# sensor_16_analog.net
KiCad netlist of a schematic drawn in EasyEDA Pro
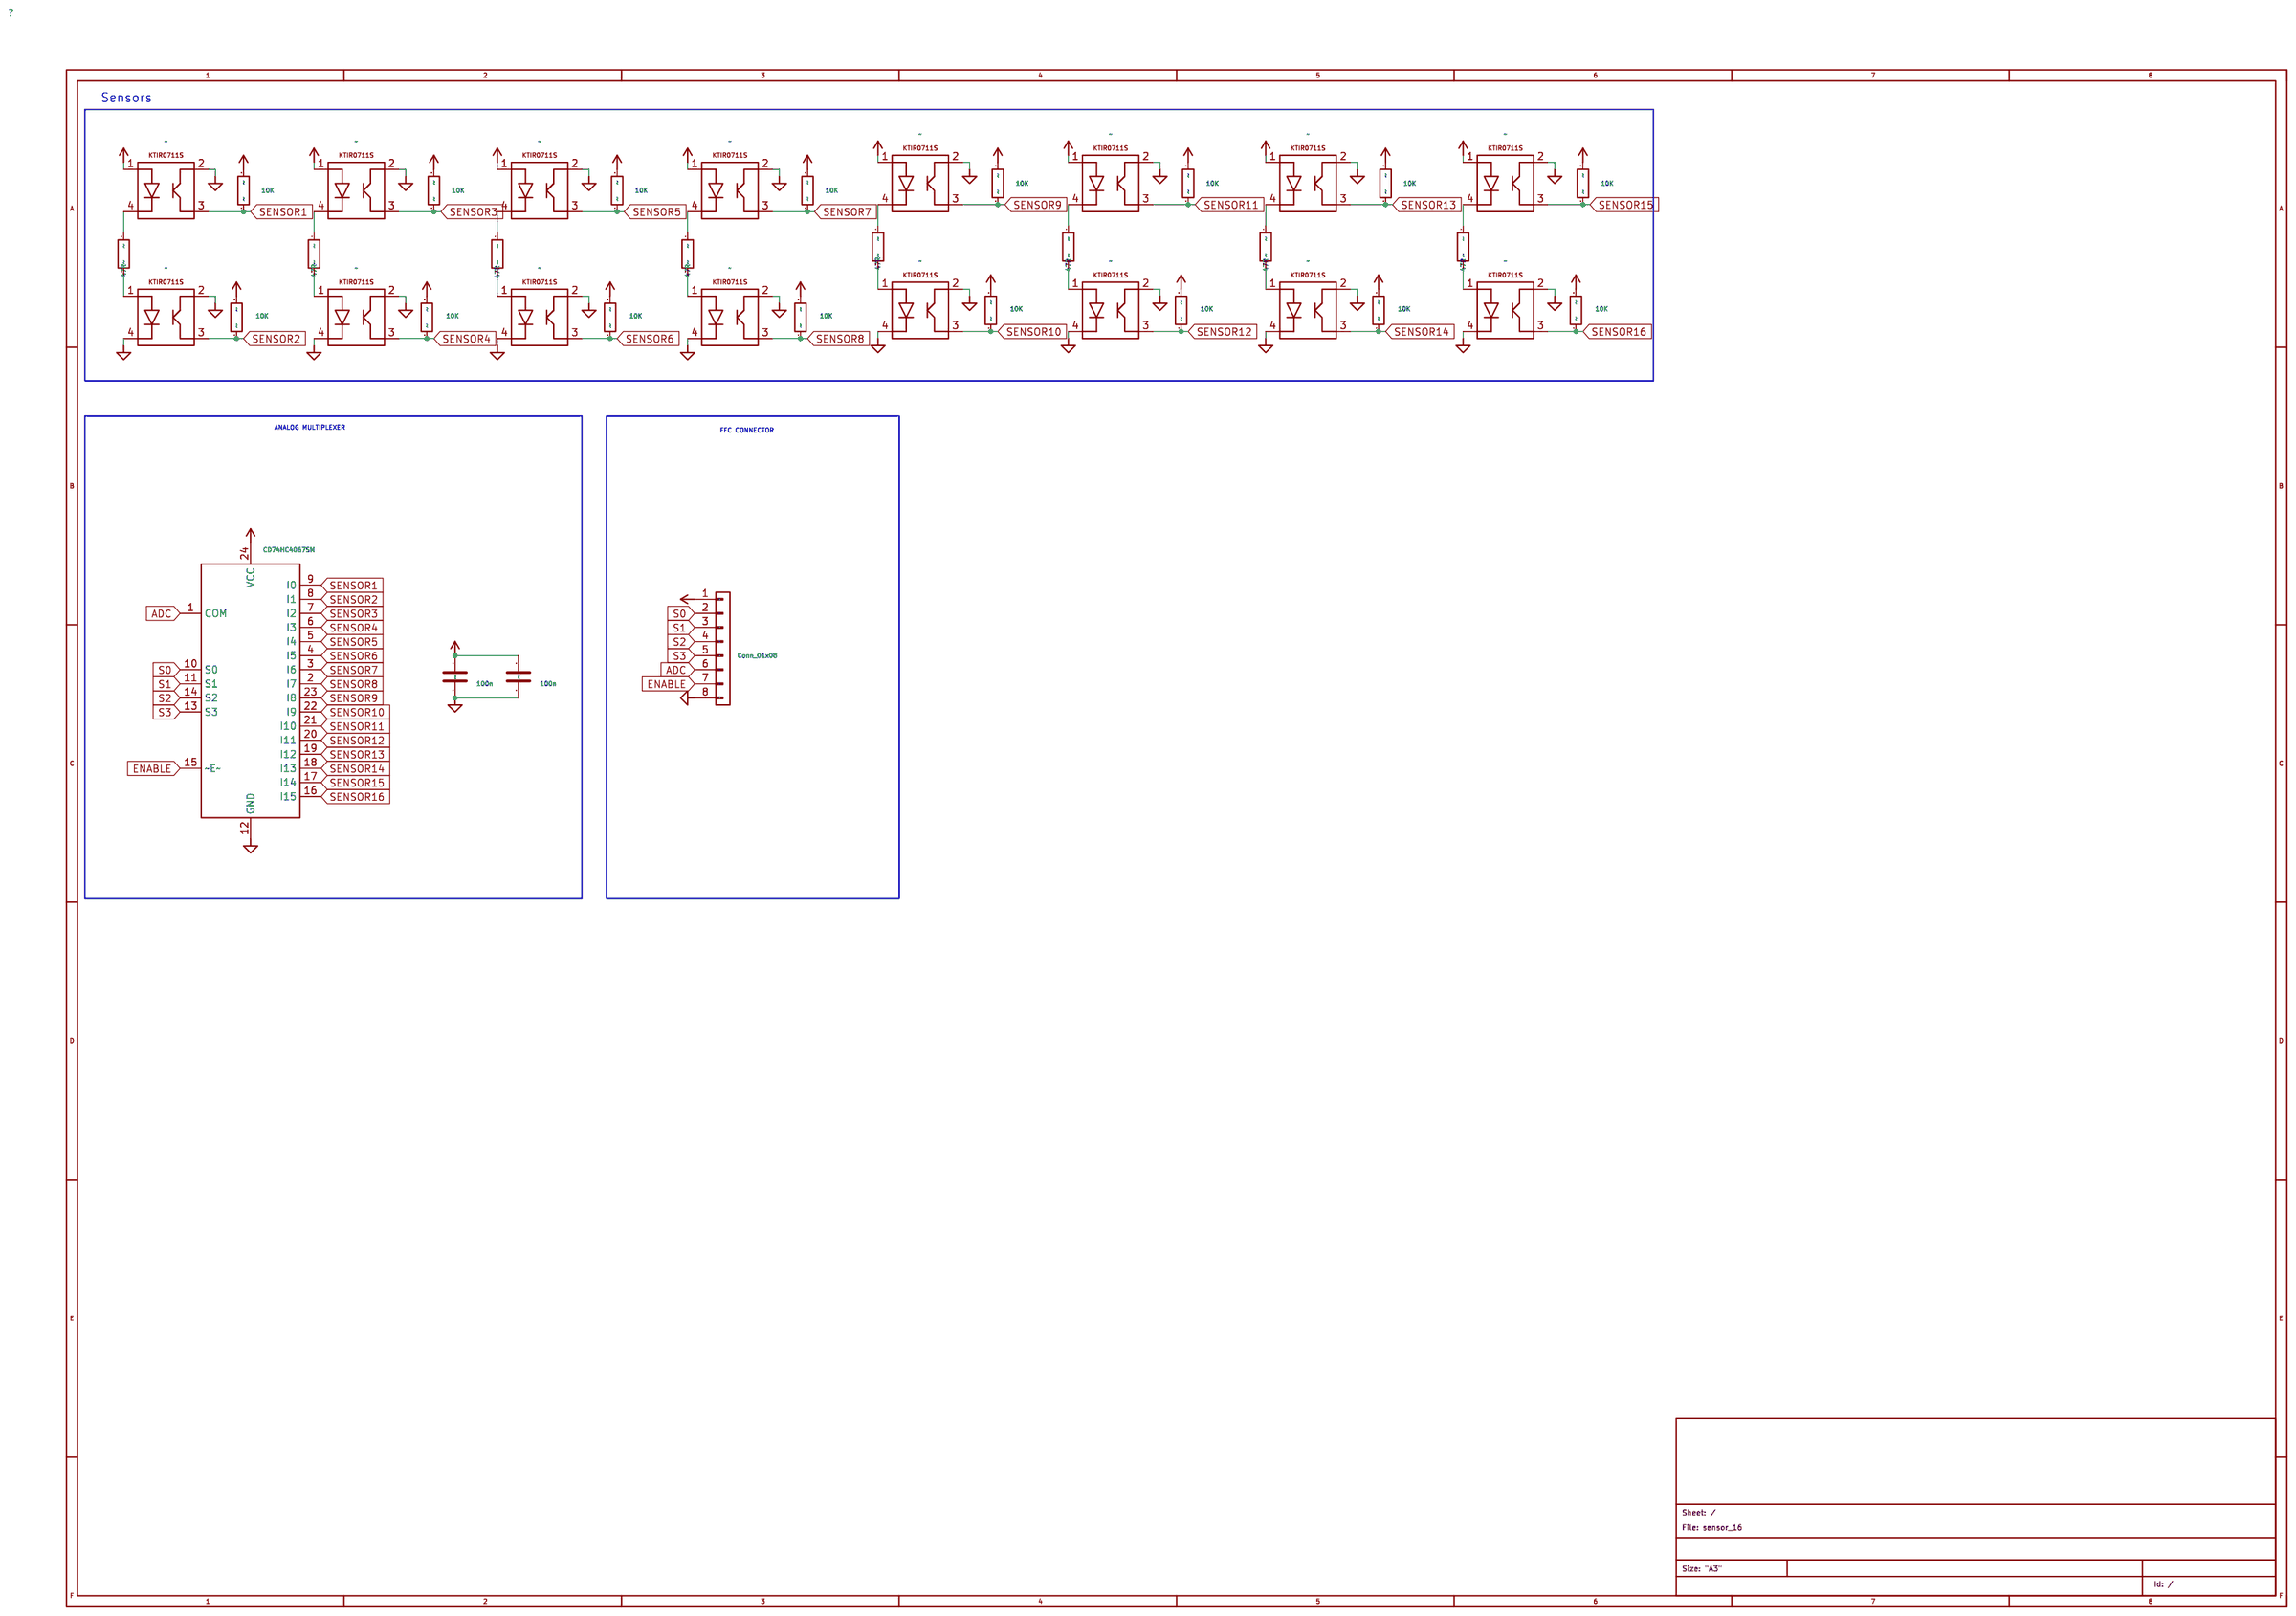
[diagram p0: schematic sheet]

(export (version "E")
  (design (tool "Eeschema 10.0.6"))
  (components
    (comp (ref "C1")
      (value "100n")
      (footprint "easyedapro:Capacitor_SMD:C_0402_1005Metric_Pad0.74x0.62mm_HandSolder")
      (description "Unpolarized capacitor")
      (libsource (lib "easyedapro") (part "Device_C"))
    )
    (comp (ref "C2")
      (value "100n")
      (footprint "easyedapro:Capacitor_SMD:C_0402_1005Metric_Pad0.74x0.62mm_HandSolder")
      (description "Unpolarized capacitor")
      (libsource (lib "easyedapro") (part "Device_C"))
    )
    (comp (ref "J1")
      (value "Conn_01x08")
      (footprint "easyedapro:Connector_FFC-FPC:Hirose_FH12-8S-0.5SH_1x08-1MP_P0.50mm_Horizontal")
      (libsource (lib "easyedapro") (part "Connector_Generic_Conn_01x08"))
    )
    (comp (ref "R1")
      (value "47R")
      (footprint "easyedapro:Resistor_SMD:R_0603_1608Metric_Pad0.98x0.95mm_HandSolder")
      (description "Resistor")
      (libsource (lib "easyedapro") (part "Device_R"))
    )
    (comp (ref "R2")
      (value "10K")
      (footprint "easyedapro:Resistor_SMD:R_0603_1608Metric_Pad0.98x0.95mm_HandSolder")
      (description "Resistor")
      (libsource (lib "easyedapro") (part "Device_R"))
    )
    (comp (ref "R3")
      (value "10K")
      (footprint "easyedapro:Resistor_SMD:R_0603_1608Metric_Pad0.98x0.95mm_HandSolder")
      (description "Resistor")
      (libsource (lib "easyedapro") (part "Device_R"))
    )
    (comp (ref "R4")
      (value "47R")
      (footprint "easyedapro:Resistor_SMD:R_0603_1608Metric_Pad0.98x0.95mm_HandSolder")
      (description "Resistor")
      (libsource (lib "easyedapro") (part "Device_R"))
    )
    (comp (ref "R5")
      (value "10K")
      (footprint "easyedapro:Resistor_SMD:R_0603_1608Metric_Pad0.98x0.95mm_HandSolder")
      (description "Resistor")
      (libsource (lib "easyedapro") (part "Device_R"))
    )
    (comp (ref "R6")
      (value "10K")
      (footprint "easyedapro:Resistor_SMD:R_0603_1608Metric_Pad0.98x0.95mm_HandSolder")
      (description "Resistor")
      (libsource (lib "easyedapro") (part "Device_R"))
    )
    (comp (ref "R7")
      (value "47R")
      (footprint "easyedapro:Resistor_SMD:R_0603_1608Metric_Pad0.98x0.95mm_HandSolder")
      (description "Resistor")
      (libsource (lib "easyedapro") (part "Device_R"))
    )
    (comp (ref "R8")
      (value "10K")
      (footprint "easyedapro:Resistor_SMD:R_0603_1608Metric_Pad0.98x0.95mm_HandSolder")
      (description "Resistor")
      (libsource (lib "easyedapro") (part "Device_R"))
    )
    (comp (ref "R9")
      (value "10K")
      (footprint "easyedapro:Resistor_SMD:R_0603_1608Metric_Pad0.98x0.95mm_HandSolder")
      (description "Resistor")
      (libsource (lib "easyedapro") (part "Device_R"))
    )
    (comp (ref "R10")
      (value "47R")
      (footprint "easyedapro:Resistor_SMD:R_0603_1608Metric_Pad0.98x0.95mm_HandSolder")
      (description "Resistor")
      (libsource (lib "easyedapro") (part "Device_R"))
    )
    (comp (ref "R11")
      (value "10K")
      (footprint "easyedapro:Resistor_SMD:R_0603_1608Metric_Pad0.98x0.95mm_HandSolder")
      (description "Resistor")
      (libsource (lib "easyedapro") (part "Device_R"))
    )
    (comp (ref "R12")
      (value "10K")
      (footprint "easyedapro:Resistor_SMD:R_0603_1608Metric_Pad0.98x0.95mm_HandSolder")
      (description "Resistor")
      (libsource (lib "easyedapro") (part "Device_R"))
    )
    (comp (ref "R13")
      (value "47R")
      (footprint "easyedapro:Resistor_SMD:R_0603_1608Metric_Pad0.98x0.95mm_HandSolder")
      (description "Resistor")
      (libsource (lib "easyedapro") (part "Device_R"))
    )
    (comp (ref "R14")
      (value "10K")
      (footprint "easyedapro:Resistor_SMD:R_0603_1608Metric_Pad0.98x0.95mm_HandSolder")
      (description "Resistor")
      (libsource (lib "easyedapro") (part "Device_R"))
    )
    (comp (ref "R15")
      (value "10K")
      (footprint "easyedapro:Resistor_SMD:R_0603_1608Metric_Pad0.98x0.95mm_HandSolder")
      (description "Resistor")
      (libsource (lib "easyedapro") (part "Device_R"))
    )
    (comp (ref "R16")
      (value "47R")
      (footprint "easyedapro:Resistor_SMD:R_0603_1608Metric_Pad0.98x0.95mm_HandSolder")
      (description "Resistor")
      (libsource (lib "easyedapro") (part "Device_R"))
    )
    (comp (ref "R17")
      (value "10K")
      (footprint "easyedapro:Resistor_SMD:R_0603_1608Metric_Pad0.98x0.95mm_HandSolder")
      (description "Resistor")
      (libsource (lib "easyedapro") (part "Device_R"))
    )
    (comp (ref "R18")
      (value "10K")
      (footprint "easyedapro:Resistor_SMD:R_0603_1608Metric_Pad0.98x0.95mm_HandSolder")
      (description "Resistor")
      (libsource (lib "easyedapro") (part "Device_R"))
    )
    (comp (ref "R19")
      (value "47R")
      (footprint "easyedapro:Resistor_SMD:R_0603_1608Metric_Pad0.98x0.95mm_HandSolder")
      (description "Resistor")
      (libsource (lib "easyedapro") (part "Device_R"))
    )
    (comp (ref "R20")
      (value "10K")
      (footprint "easyedapro:Resistor_SMD:R_0603_1608Metric_Pad0.98x0.95mm_HandSolder")
      (description "Resistor")
      (libsource (lib "easyedapro") (part "Device_R"))
    )
    (comp (ref "R21")
      (value "10K")
      (footprint "easyedapro:Resistor_SMD:R_0603_1608Metric_Pad0.98x0.95mm_HandSolder")
      (description "Resistor")
      (libsource (lib "easyedapro") (part "Device_R"))
    )
    (comp (ref "R22")
      (value "47R")
      (footprint "easyedapro:Resistor_SMD:R_0603_1608Metric_Pad0.98x0.95mm_HandSolder")
      (description "Resistor")
      (libsource (lib "easyedapro") (part "Device_R"))
    )
    (comp (ref "R23")
      (value "10K")
      (footprint "easyedapro:Resistor_SMD:R_0603_1608Metric_Pad0.98x0.95mm_HandSolder")
      (description "Resistor")
      (libsource (lib "easyedapro") (part "Device_R"))
    )
    (comp (ref "R24")
      (value "10K")
      (footprint "easyedapro:Resistor_SMD:R_0603_1608Metric_Pad0.98x0.95mm_HandSolder")
      (description "Resistor")
      (libsource (lib "easyedapro") (part "Device_R"))
    )
    (comp (ref "U1")
      (value "~")
      (footprint "easyedapro:SensorLib:KTIR0711S")
      (libsource (lib "easyedapro") (part "Sensor_Library_KTIR0711S"))
    )
    (comp (ref "U2")
      (value "~")
      (footprint "easyedapro:SensorLib:KTIR0711S")
      (libsource (lib "easyedapro") (part "Sensor_Library_KTIR0711S"))
    )
    (comp (ref "U3")
      (value "~")
      (footprint "easyedapro:SensorLib:KTIR0711S")
      (libsource (lib "easyedapro") (part "Sensor_Library_KTIR0711S"))
    )
    (comp (ref "U4")
      (value "~")
      (footprint "easyedapro:SensorLib:KTIR0711S")
      (libsource (lib "easyedapro") (part "Sensor_Library_KTIR0711S"))
    )
    (comp (ref "U5")
      (value "~")
      (footprint "easyedapro:SensorLib:KTIR0711S")
      (libsource (lib "easyedapro") (part "Sensor_Library_KTIR0711S"))
    )
    (comp (ref "U6")
      (value "~")
      (footprint "easyedapro:SensorLib:KTIR0711S")
      (libsource (lib "easyedapro") (part "Sensor_Library_KTIR0711S"))
    )
    (comp (ref "U7")
      (value "~")
      (footprint "easyedapro:SensorLib:KTIR0711S")
      (libsource (lib "easyedapro") (part "Sensor_Library_KTIR0711S"))
    )
    (comp (ref "U8")
      (value "~")
      (footprint "easyedapro:SensorLib:KTIR0711S")
      (libsource (lib "easyedapro") (part "Sensor_Library_KTIR0711S"))
    )
    (comp (ref "U9")
      (value "~")
      (footprint "easyedapro:SensorLib:KTIR0711S")
      (libsource (lib "easyedapro") (part "Sensor_Library_KTIR0711S"))
    )
    (comp (ref "U10")
      (value "~")
      (footprint "easyedapro:SensorLib:KTIR0711S")
      (libsource (lib "easyedapro") (part "Sensor_Library_KTIR0711S"))
    )
    (comp (ref "U11")
      (value "~")
      (footprint "easyedapro:SensorLib:KTIR0711S")
      (libsource (lib "easyedapro") (part "Sensor_Library_KTIR0711S"))
    )
    (comp (ref "U12")
      (value "~")
      (footprint "easyedapro:SensorLib:KTIR0711S")
      (libsource (lib "easyedapro") (part "Sensor_Library_KTIR0711S"))
    )
    (comp (ref "U13")
      (value "~")
      (footprint "easyedapro:SensorLib:KTIR0711S")
      (libsource (lib "easyedapro") (part "Sensor_Library_KTIR0711S"))
    )
    (comp (ref "U14")
      (value "~")
      (footprint "easyedapro:SensorLib:KTIR0711S")
      (libsource (lib "easyedapro") (part "Sensor_Library_KTIR0711S"))
    )
    (comp (ref "U15")
      (value "~")
      (footprint "easyedapro:SensorLib:KTIR0711S")
      (libsource (lib "easyedapro") (part "Sensor_Library_KTIR0711S"))
    )
    (comp (ref "U16")
      (value "~")
      (footprint "easyedapro:SensorLib:KTIR0711S")
      (libsource (lib "easyedapro") (part "Sensor_Library_KTIR0711S"))
    )
    (comp (ref "U17")
      (value "CD74HC4067SM")
      (footprint "easyedapro:footprints:TSSOP24_4P5X7P9_TEX-M")
      (description "High-Speed CMOS Logic 16-Channel Analog Multiplexer/Demultiplexer, SSOP-24")
      (libsource (lib "easyedapro") (part "74xx_CD74HC4067SM"))
    )
  )
  (nets
    (net (code "1") (name "ADC") (class "Default")
      (node (ref "J1") (pin "6") (pinfunction "Pin_6_6") (pintype "unspecified"))
      (node (ref "U17") (pin "1") (pinfunction "COM_1") (pintype "unspecified"))
    )
    (net (code "2") (name "ENABLE") (class "Default")
      (node (ref "J1") (pin "7") (pinfunction "Pin_7_7") (pintype "unspecified"))
      (node (ref "U17") (pin "15") (pinfunction "~E~_15") (pintype "input"))
    )
    (net (code "3") (name "Net-(R1-~-Pad1)") (class "Default")
      (node (ref "R1") (pin "1") (pinfunction "~_1") (pintype "unspecified"))
      (node (ref "U1") (pin "4") (pintype "input"))
    )
    (net (code "4") (name "Net-(R1-~-Pad2)") (class "Default")
      (node (ref "R1") (pin "2") (pinfunction "~_2") (pintype "unspecified"))
      (node (ref "U2") (pin "1") (pintype "input"))
    )
    (net (code "5") (name "Net-(R4-~-Pad1)") (class "Default")
      (node (ref "R4") (pin "1") (pinfunction "~_1") (pintype "unspecified"))
      (node (ref "U3") (pin "4") (pintype "input"))
    )
    (net (code "6") (name "Net-(R4-~-Pad2)") (class "Default")
      (node (ref "R4") (pin "2") (pinfunction "~_2") (pintype "unspecified"))
      (node (ref "U4") (pin "1") (pintype "input"))
    )
    (net (code "7") (name "Net-(R7-~-Pad1)") (class "Default")
      (node (ref "R7") (pin "1") (pinfunction "~_1") (pintype "unspecified"))
      (node (ref "U5") (pin "4") (pintype "input"))
    )
    (net (code "8") (name "Net-(R7-~-Pad2)") (class "Default")
      (node (ref "R7") (pin "2") (pinfunction "~_2") (pintype "unspecified"))
      (node (ref "U6") (pin "1") (pintype "input"))
    )
    (net (code "9") (name "Net-(R10-~-Pad1)") (class "Default")
      (node (ref "R10") (pin "1") (pinfunction "~_1") (pintype "unspecified"))
      (node (ref "U7") (pin "4") (pintype "input"))
    )
    (net (code "10") (name "Net-(R10-~-Pad2)") (class "Default")
      (node (ref "R10") (pin "2") (pinfunction "~_2") (pintype "unspecified"))
      (node (ref "U8") (pin "1") (pintype "input"))
    )
    (net (code "11") (name "Net-(R13-~-Pad1)") (class "Default")
      (node (ref "R13") (pin "1") (pinfunction "~_1") (pintype "unspecified"))
      (node (ref "U9") (pin "4") (pintype "input"))
    )
    (net (code "12") (name "Net-(R13-~-Pad2)") (class "Default")
      (node (ref "R13") (pin "2") (pinfunction "~_2") (pintype "unspecified"))
      (node (ref "U10") (pin "1") (pintype "input"))
    )
    (net (code "13") (name "Net-(R16-~-Pad1)") (class "Default")
      (node (ref "R16") (pin "1") (pinfunction "~_1") (pintype "unspecified"))
      (node (ref "U11") (pin "4") (pintype "input"))
    )
    (net (code "14") (name "Net-(R16-~-Pad2)") (class "Default")
      (node (ref "R16") (pin "2") (pinfunction "~_2") (pintype "unspecified"))
      (node (ref "U12") (pin "1") (pintype "input"))
    )
    (net (code "15") (name "Net-(R19-~-Pad1)") (class "Default")
      (node (ref "R19") (pin "1") (pinfunction "~_1") (pintype "unspecified"))
      (node (ref "U13") (pin "4") (pintype "input"))
    )
    (net (code "16") (name "Net-(R19-~-Pad2)") (class "Default")
      (node (ref "R19") (pin "2") (pinfunction "~_2") (pintype "unspecified"))
      (node (ref "U14") (pin "1") (pintype "input"))
    )
    (net (code "17") (name "Net-(R22-~-Pad1)") (class "Default")
      (node (ref "R22") (pin "1") (pinfunction "~_1") (pintype "unspecified"))
      (node (ref "U15") (pin "4") (pintype "input"))
    )
    (net (code "18") (name "Net-(R22-~-Pad2)") (class "Default")
      (node (ref "R22") (pin "2") (pinfunction "~_2") (pintype "unspecified"))
      (node (ref "U16") (pin "1") (pintype "input"))
    )
    (net (code "19") (name "POWER_+3.3V") (class "Default")
      (node (ref "C1") (pin "1") (pinfunction "~_1") (pintype "unspecified"))
      (node (ref "C2") (pin "1") (pinfunction "~_1") (pintype "unspecified"))
      (node (ref "J1") (pin "1") (pinfunction "Pin_1_1") (pintype "unspecified"))
      (node (ref "R11") (pin "2") (pinfunction "~_2") (pintype "unspecified"))
      (node (ref "R12") (pin "2") (pinfunction "~_2") (pintype "unspecified"))
      (node (ref "R14") (pin "2") (pinfunction "~_2") (pintype "unspecified"))
      (node (ref "R15") (pin "2") (pinfunction "~_2") (pintype "unspecified"))
      (node (ref "R17") (pin "2") (pinfunction "~_2") (pintype "unspecified"))
      (node (ref "R18") (pin "2") (pinfunction "~_2") (pintype "unspecified"))
      (node (ref "R2") (pin "2") (pinfunction "~_2") (pintype "unspecified"))
      (node (ref "R20") (pin "2") (pinfunction "~_2") (pintype "unspecified"))
      (node (ref "R21") (pin "2") (pinfunction "~_2") (pintype "unspecified"))
      (node (ref "R23") (pin "2") (pinfunction "~_2") (pintype "unspecified"))
      (node (ref "R24") (pin "2") (pinfunction "~_2") (pintype "unspecified"))
      (node (ref "R3") (pin "2") (pinfunction "~_2") (pintype "unspecified"))
      (node (ref "R5") (pin "2") (pinfunction "~_2") (pintype "unspecified"))
      (node (ref "R6") (pin "2") (pinfunction "~_2") (pintype "unspecified"))
      (node (ref "R8") (pin "2") (pinfunction "~_2") (pintype "unspecified"))
      (node (ref "R9") (pin "2") (pinfunction "~_2") (pintype "unspecified"))
      (node (ref "U1") (pin "1") (pintype "input"))
      (node (ref "U11") (pin "1") (pintype "input"))
      (node (ref "U13") (pin "1") (pintype "input"))
      (node (ref "U15") (pin "1") (pintype "input"))
      (node (ref "U17") (pin "24") (pinfunction "VCC_24") (pintype "unspecified"))
      (node (ref "U3") (pin "1") (pintype "input"))
      (node (ref "U5") (pin "1") (pintype "input"))
      (node (ref "U7") (pin "1") (pintype "input"))
      (node (ref "U9") (pin "1") (pintype "input"))
    )
    (net (code "20") (name "POWER_GND") (class "Default")
      (node (ref "C1") (pin "2") (pinfunction "~_2") (pintype "unspecified"))
      (node (ref "C2") (pin "2") (pinfunction "~_2") (pintype "unspecified"))
      (node (ref "J1") (pin "8") (pinfunction "Pin_8_8") (pintype "unspecified"))
      (node (ref "U1") (pin "2") (pintype "input"))
      (node (ref "U10") (pin "2") (pintype "input"))
      (node (ref "U10") (pin "4") (pintype "input"))
      (node (ref "U11") (pin "2") (pintype "input"))
      (node (ref "U12") (pin "2") (pintype "input"))
      (node (ref "U12") (pin "4") (pintype "input"))
      (node (ref "U13") (pin "2") (pintype "input"))
      (node (ref "U14") (pin "2") (pintype "input"))
      (node (ref "U14") (pin "4") (pintype "input"))
      (node (ref "U15") (pin "2") (pintype "input"))
      (node (ref "U16") (pin "2") (pintype "input"))
      (node (ref "U16") (pin "4") (pintype "input"))
      (node (ref "U17") (pin "12") (pinfunction "GND_12") (pintype "unspecified"))
      (node (ref "U2") (pin "2") (pintype "input"))
      (node (ref "U2") (pin "4") (pintype "input"))
      (node (ref "U3") (pin "2") (pintype "input"))
      (node (ref "U4") (pin "2") (pintype "input"))
      (node (ref "U4") (pin "4") (pintype "input"))
      (node (ref "U5") (pin "2") (pintype "input"))
      (node (ref "U6") (pin "2") (pintype "input"))
      (node (ref "U6") (pin "4") (pintype "input"))
      (node (ref "U7") (pin "2") (pintype "input"))
      (node (ref "U8") (pin "2") (pintype "input"))
      (node (ref "U8") (pin "4") (pintype "input"))
      (node (ref "U9") (pin "2") (pintype "input"))
    )
    (net (code "21") (name "S0") (class "Default")
      (node (ref "J1") (pin "2") (pinfunction "Pin_2_2") (pintype "unspecified"))
      (node (ref "U17") (pin "10") (pinfunction "S0_10") (pintype "input"))
    )
    (net (code "22") (name "S1") (class "Default")
      (node (ref "J1") (pin "3") (pinfunction "Pin_3_3") (pintype "unspecified"))
      (node (ref "U17") (pin "11") (pinfunction "S1_11") (pintype "input"))
    )
    (net (code "23") (name "S2") (class "Default")
      (node (ref "J1") (pin "4") (pinfunction "Pin_4_4") (pintype "unspecified"))
      (node (ref "U17") (pin "14") (pinfunction "S2_14") (pintype "input"))
    )
    (net (code "24") (name "S3") (class "Default")
      (node (ref "J1") (pin "5") (pinfunction "Pin_5_5") (pintype "unspecified"))
      (node (ref "U17") (pin "13") (pinfunction "S3_13") (pintype "input"))
    )
    (net (code "25") (name "SENSOR1") (class "Default")
      (node (ref "R3") (pin "1") (pinfunction "~_1") (pintype "unspecified"))
      (node (ref "U1") (pin "3") (pintype "input"))
      (node (ref "U17") (pin "9") (pinfunction "I0_9") (pintype "unspecified"))
    )
    (net (code "26") (name "SENSOR2") (class "Default")
      (node (ref "R2") (pin "1") (pinfunction "~_1") (pintype "unspecified"))
      (node (ref "U17") (pin "8") (pinfunction "I1_8") (pintype "unspecified"))
      (node (ref "U2") (pin "3") (pintype "input"))
    )
    (net (code "27") (name "SENSOR3") (class "Default")
      (node (ref "R6") (pin "1") (pinfunction "~_1") (pintype "unspecified"))
      (node (ref "U17") (pin "7") (pinfunction "I2_7") (pintype "unspecified"))
      (node (ref "U3") (pin "3") (pintype "input"))
    )
    (net (code "28") (name "SENSOR4") (class "Default")
      (node (ref "R5") (pin "1") (pinfunction "~_1") (pintype "unspecified"))
      (node (ref "U17") (pin "6") (pinfunction "I3_6") (pintype "unspecified"))
      (node (ref "U4") (pin "3") (pintype "input"))
    )
    (net (code "29") (name "SENSOR5") (class "Default")
      (node (ref "R9") (pin "1") (pinfunction "~_1") (pintype "unspecified"))
      (node (ref "U17") (pin "5") (pinfunction "I4_5") (pintype "unspecified"))
      (node (ref "U5") (pin "3") (pintype "input"))
    )
    (net (code "30") (name "SENSOR6") (class "Default")
      (node (ref "R8") (pin "1") (pinfunction "~_1") (pintype "unspecified"))
      (node (ref "U17") (pin "4") (pinfunction "I5_4") (pintype "unspecified"))
      (node (ref "U6") (pin "3") (pintype "input"))
    )
    (net (code "31") (name "SENSOR7") (class "Default")
      (node (ref "R12") (pin "1") (pinfunction "~_1") (pintype "unspecified"))
      (node (ref "U17") (pin "3") (pinfunction "I6_3") (pintype "unspecified"))
      (node (ref "U7") (pin "3") (pintype "input"))
    )
    (net (code "32") (name "SENSOR8") (class "Default")
      (node (ref "R11") (pin "1") (pinfunction "~_1") (pintype "unspecified"))
      (node (ref "U17") (pin "2") (pinfunction "I7_2") (pintype "unspecified"))
      (node (ref "U8") (pin "3") (pintype "input"))
    )
    (net (code "33") (name "SENSOR9") (class "Default")
      (node (ref "R15") (pin "1") (pinfunction "~_1") (pintype "unspecified"))
      (node (ref "U17") (pin "23") (pinfunction "I8_23") (pintype "unspecified"))
      (node (ref "U9") (pin "3") (pintype "input"))
    )
    (net (code "34") (name "SENSOR10") (class "Default")
      (node (ref "R14") (pin "1") (pinfunction "~_1") (pintype "unspecified"))
      (node (ref "U10") (pin "3") (pintype "input"))
      (node (ref "U17") (pin "22") (pinfunction "I9_22") (pintype "unspecified"))
    )
    (net (code "35") (name "SENSOR11") (class "Default")
      (node (ref "R18") (pin "1") (pinfunction "~_1") (pintype "unspecified"))
      (node (ref "U11") (pin "3") (pintype "input"))
      (node (ref "U17") (pin "21") (pinfunction "I10_21") (pintype "unspecified"))
    )
    (net (code "36") (name "SENSOR12") (class "Default")
      (node (ref "R17") (pin "1") (pinfunction "~_1") (pintype "unspecified"))
      (node (ref "U12") (pin "3") (pintype "input"))
      (node (ref "U17") (pin "20") (pinfunction "I11_20") (pintype "unspecified"))
    )
    (net (code "37") (name "SENSOR13") (class "Default")
      (node (ref "R21") (pin "1") (pinfunction "~_1") (pintype "unspecified"))
      (node (ref "U13") (pin "3") (pintype "input"))
      (node (ref "U17") (pin "19") (pinfunction "I12_19") (pintype "unspecified"))
    )
    (net (code "38") (name "SENSOR14") (class "Default")
      (node (ref "R20") (pin "1") (pinfunction "~_1") (pintype "unspecified"))
      (node (ref "U14") (pin "3") (pintype "input"))
      (node (ref "U17") (pin "18") (pinfunction "I13_18") (pintype "unspecified"))
    )
    (net (code "39") (name "SENSOR15") (class "Default")
      (node (ref "R24") (pin "1") (pinfunction "~_1") (pintype "unspecified"))
      (node (ref "U15") (pin "3") (pintype "input"))
      (node (ref "U17") (pin "17") (pinfunction "I14_17") (pintype "unspecified"))
    )
    (net (code "40") (name "SENSOR16") (class "Default")
      (node (ref "R23") (pin "1") (pinfunction "~_1") (pintype "unspecified"))
      (node (ref "U16") (pin "3") (pintype "input"))
      (node (ref "U17") (pin "16") (pinfunction "I15_16") (pintype "unspecified"))
    )
  )
)
